# relay_based_circuit_-_Copy.net
KiCad netlist of a schematic drawn in EAGLE
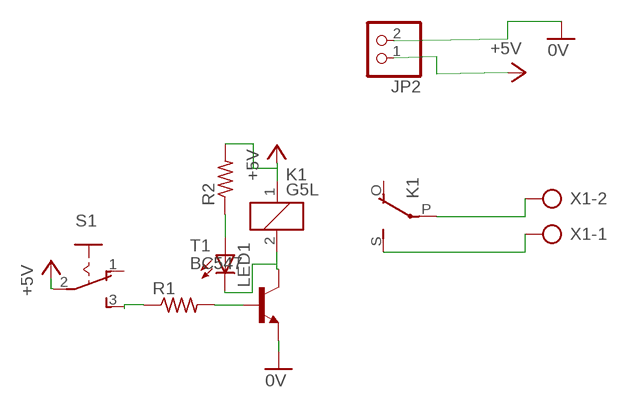
[diagram p0: schematic, sheet 1]

(export (version "E")
  (design (tool "Eeschema 10.0.6"))
  (components
    (comp (ref "JP2")
      (value "PINHD-1X2")
      (footprint "eagle-import:1X02")
      (libsource (lib "eagle-import") (part "PINHD-1X2"))
    )
    (comp (ref "K1")
      (value "G5L")
      (footprint "eagle-import:G5LE")
      (libsource (lib "eagle-import") (part "G5L"))
    )
    (comp (ref "LED1")
      (value "LED3MM")
      (footprint "eagle-import:LED3MM")
      (libsource (lib "eagle-import") (part "LED3MM"))
    )
    (comp (ref "R1")
      (value "R-US_0207/10")
      (footprint "eagle-import:0207_10")
      (libsource (lib "eagle-import") (part "R-US_0207/10"))
    )
    (comp (ref "R2")
      (value "R-US_0207/10")
      (footprint "eagle-import:0207_10")
      (libsource (lib "eagle-import") (part "R-US_0207/10"))
    )
    (comp (ref "S1")
      (value "M251")
      (footprint "eagle-import:M251")
      (libsource (lib "eagle-import") (part "M251"))
    )
    (comp (ref "T1")
      (value "BC547")
      (footprint "eagle-import:TO92")
      (libsource (lib "eagle-import") (part "BC547"))
    )
    (comp (ref "X1")
      (value "AK500/2")
      (footprint "eagle-import:AK500_2")
      (libsource (lib "eagle-import") (part "AK500/2"))
    )
  )
  (nets
    (net (code "1") (name "+5V") (class "Default")
      (node (ref "JP2") (pin "1") (pinfunction "1_1") (pintype "passive"))
      (node (ref "K1") (pin "1") (pinfunction "1_1") (pintype "passive"))
      (node (ref "R2") (pin "2") (pinfunction "2_2") (pintype "passive"))
      (node (ref "S1") (pin "2") (pinfunction "P_2") (pintype "passive"))
    )
    (net (code "2") (name "0V") (class "Default")
      (node (ref "JP2") (pin "2") (pinfunction "2_2") (pintype "passive"))
      (node (ref "T1") (pin "1") (pinfunction "E_1") (pintype "passive"))
    )
    (net (code "3") (name "Net-(LED1-C)") (class "Default")
      (node (ref "K1") (pin "2") (pinfunction "2_2") (pintype "passive"))
      (node (ref "LED1") (pin "K") (pinfunction "C_K") (pintype "passive"))
      (node (ref "T1") (pin "3") (pinfunction "C_3") (pintype "passive"))
    )
    (net (code "4") (name "Net-(LED1-PadA)") (class "Default")
      (node (ref "LED1") (pin "A") (pinfunction "A_A") (pintype "passive"))
      (node (ref "R2") (pin "1") (pinfunction "1_1") (pintype "passive"))
    )
    (net (code "5") (name "Net-(S1-S)") (class "Default")
      (node (ref "R1") (pin "1") (pinfunction "1_1") (pintype "passive"))
      (node (ref "S1") (pin "3") (pinfunction "S_3") (pintype "passive"))
    )
    (net (code "6") (name "Net-(T1-B)") (class "Default")
      (node (ref "R1") (pin "2") (pinfunction "2_2") (pintype "passive"))
      (node (ref "T1") (pin "2") (pinfunction "B_2") (pintype "passive"))
    )
    (net (code "7") (name "Net-(X1A-KL)") (class "Default")
      (node (ref "K1") (pin "S") (pinfunction "S_S") (pintype "passive"))
      (node (ref "X1") (pin "1") (pinfunction "KL_1") (pintype "passive"))
    )
    (net (code "8") (name "Net-(X1B-KL)") (class "Default")
      (node (ref "K1") (pin "P") (pinfunction "P_P") (pintype "passive"))
      (node (ref "X1") (pin "2") (pinfunction "KL_2") (pintype "passive"))
    )
    (net (code "9") (name "unconnected-(K1-PadO)") (class "Default")
      (node (ref "K1") (pin "O") (pinfunction "O_O") (pintype "passive"))
    )
    (net (code "10") (name "unconnected-(S1-O-Pad1)") (class "Default")
      (node (ref "S1") (pin "1") (pinfunction "O_1") (pintype "passive"))
    )
  )
)
